# SCH_Atmega_board.net
KiCad netlist of a schematic drawn in Altium Designer
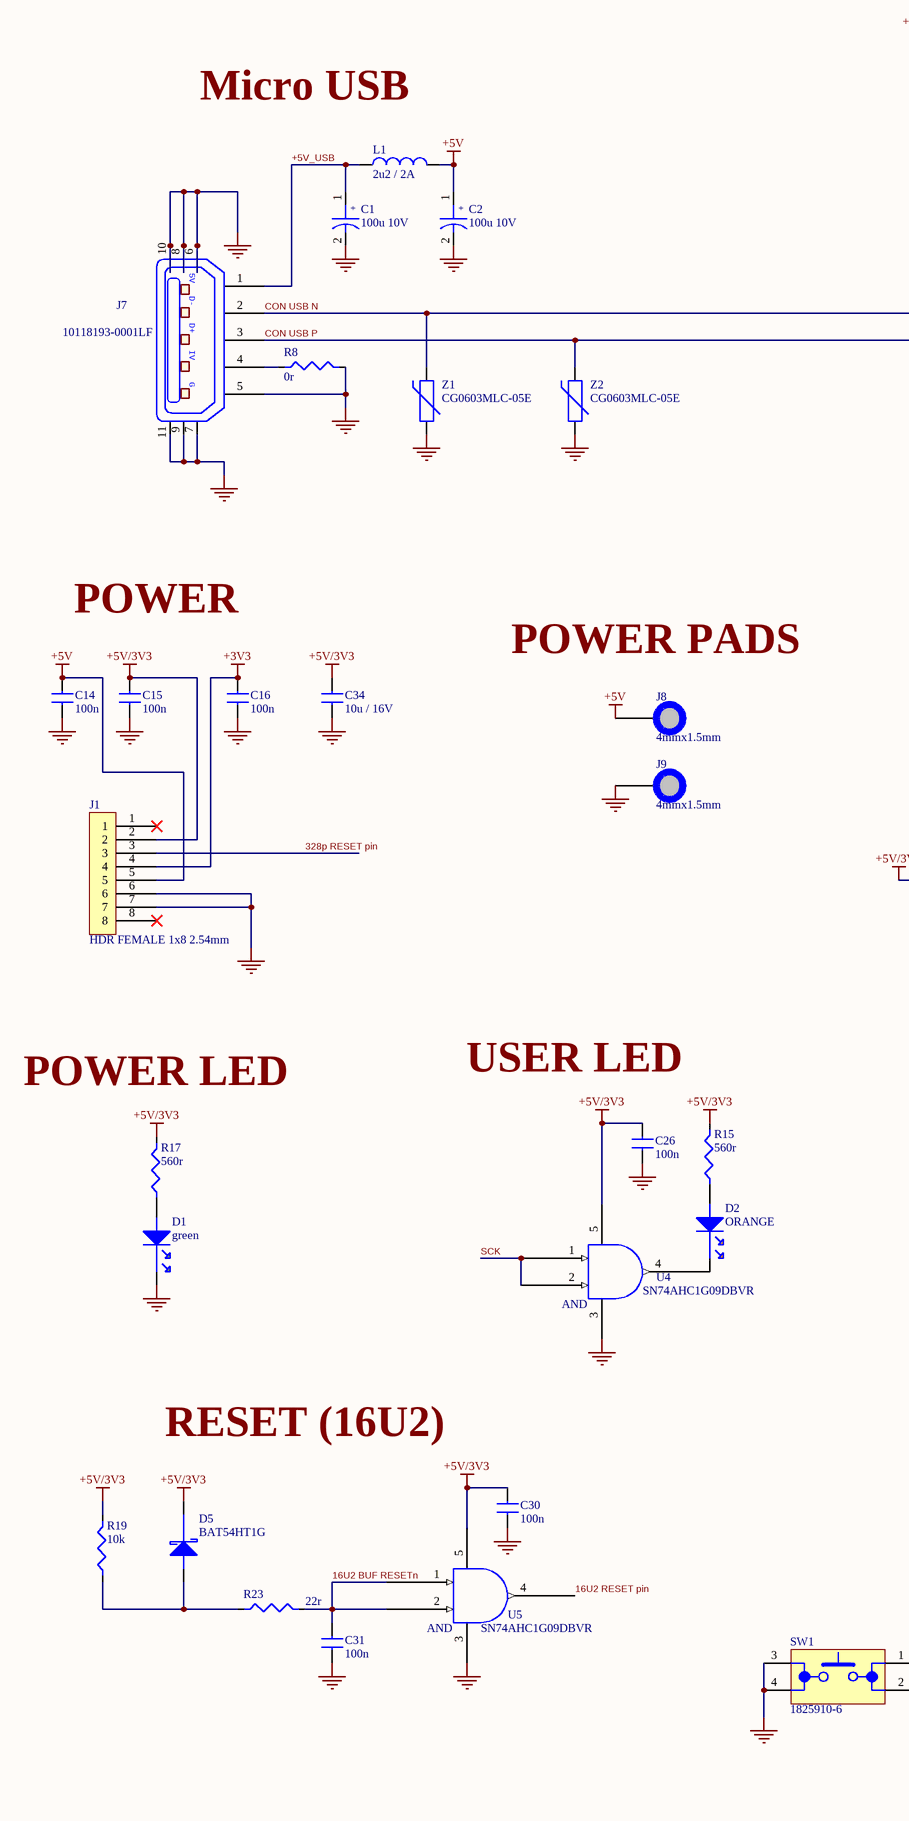
[diagram p0: SCH_Atmega_board.SchDoc, left]
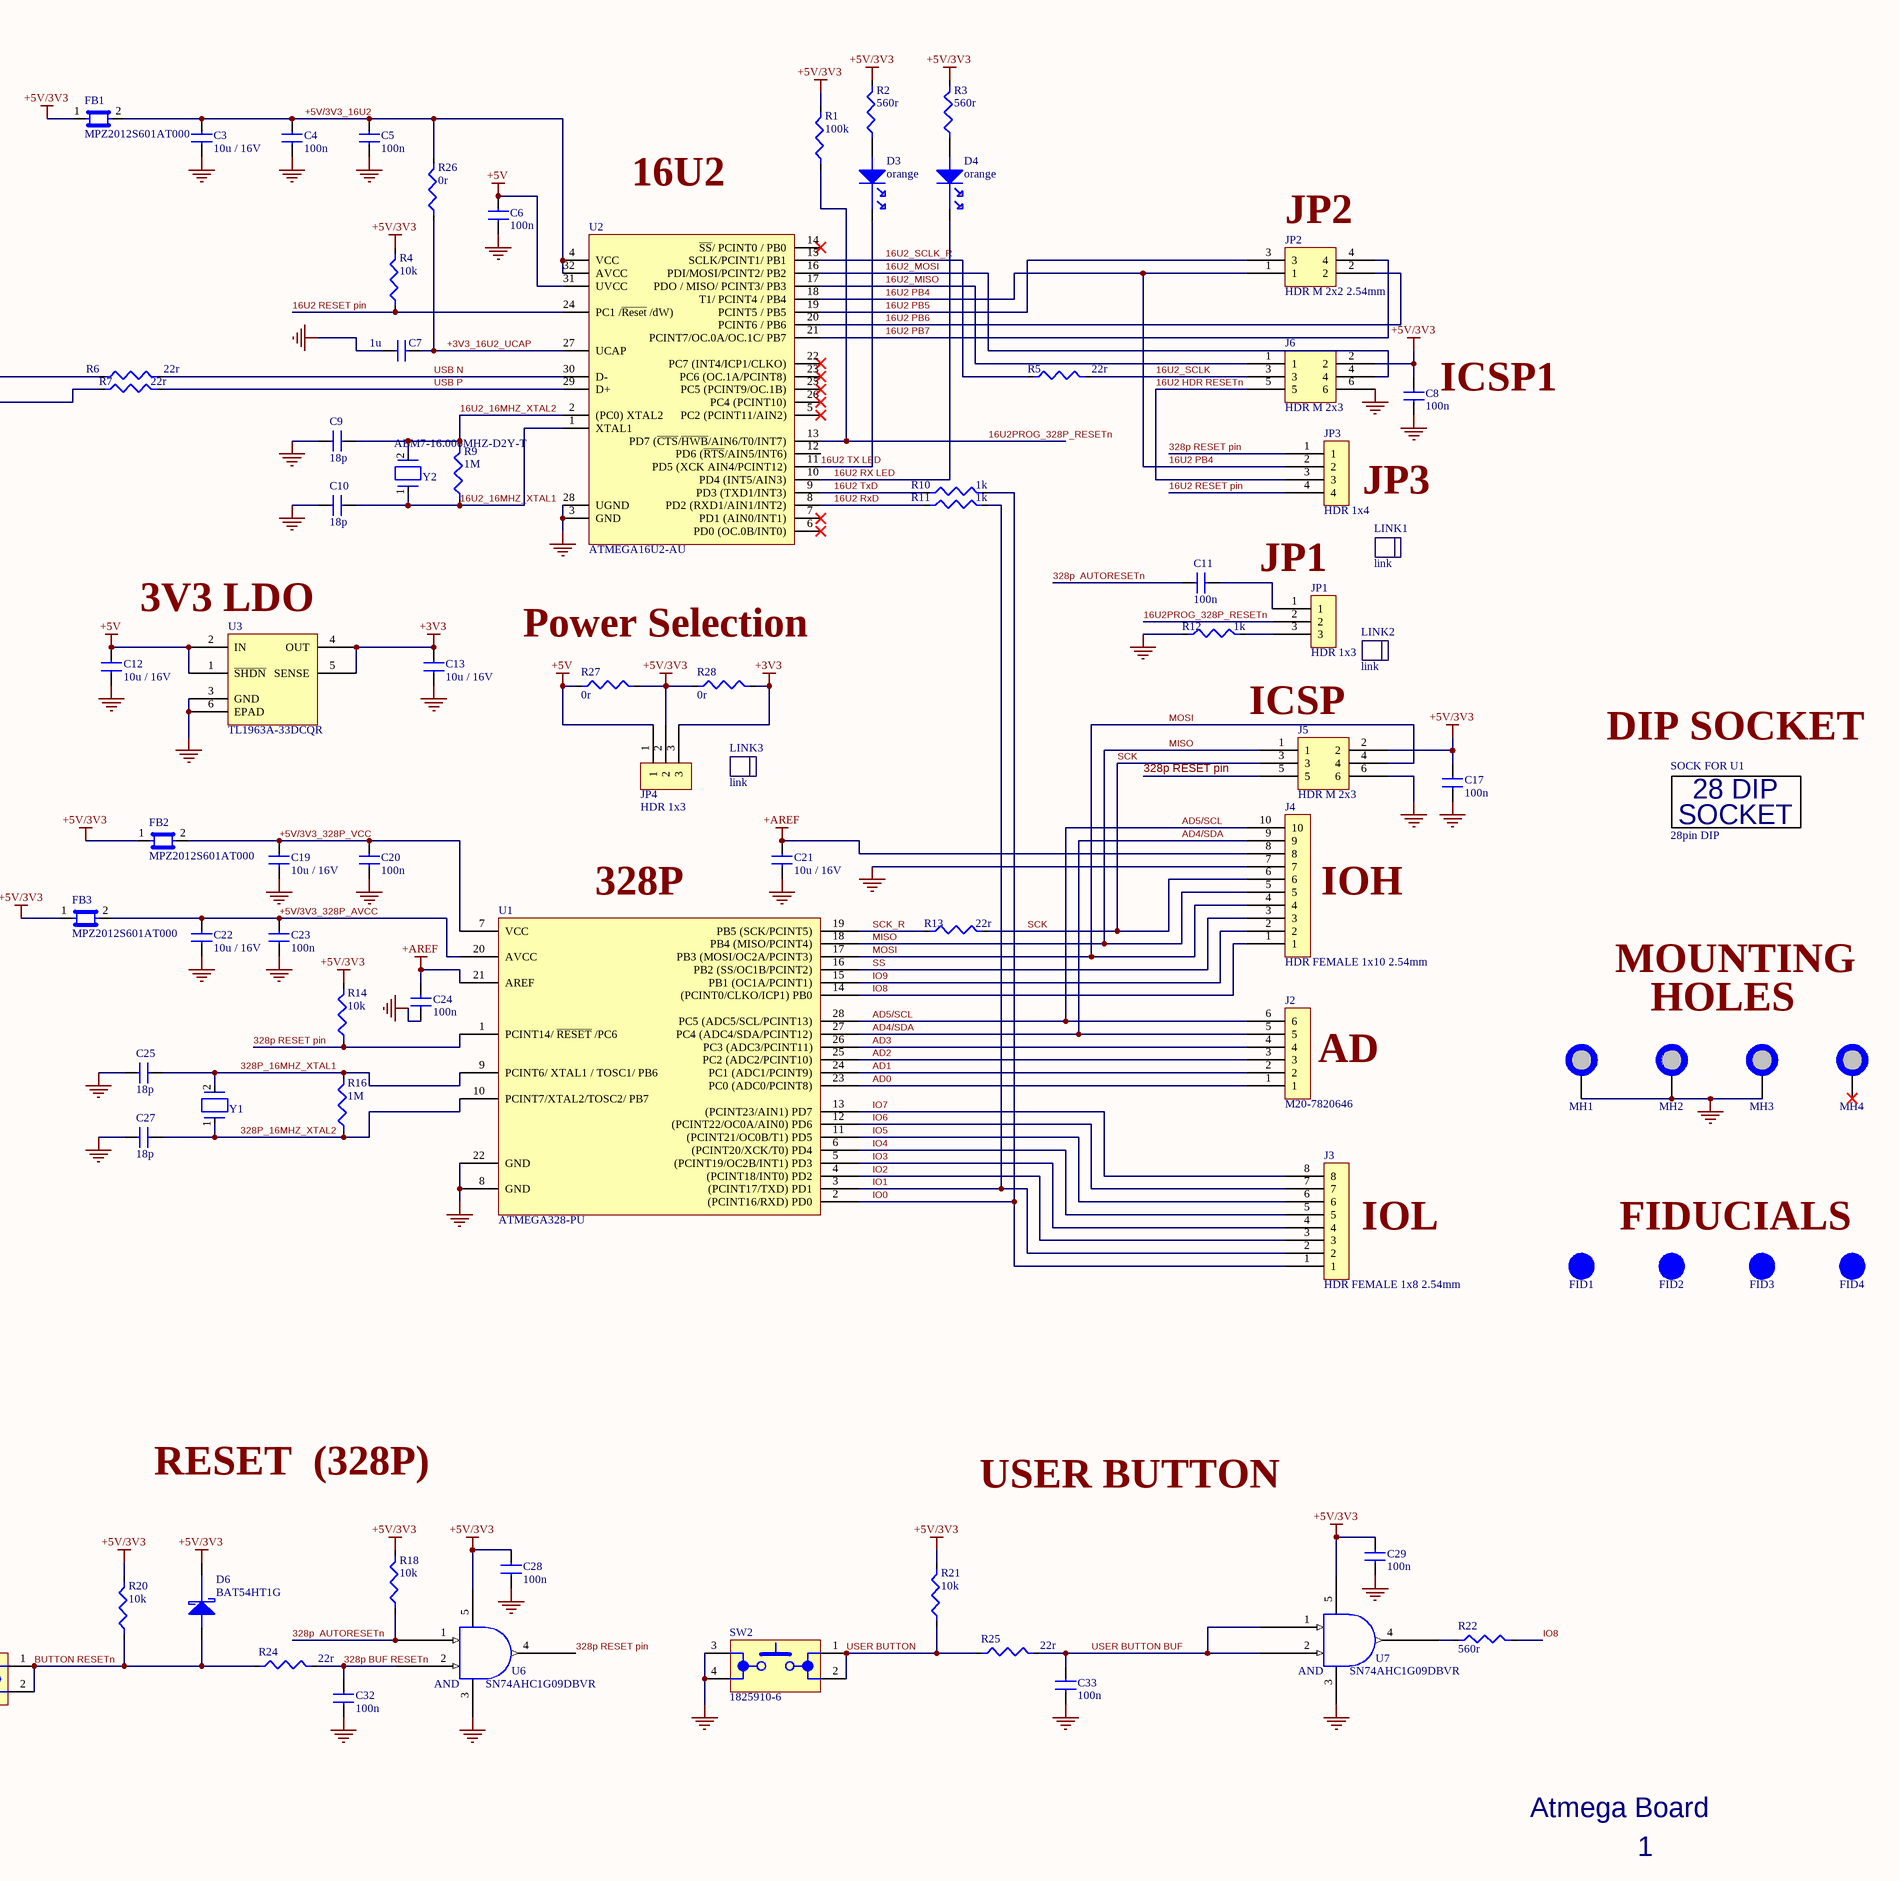
[diagram p1: SCH_Atmega_board.SchDoc, right]

(export (version "E")
  (design (tool "Eeschema 10.0.6"))
  (components
    (comp (ref "C1")
      (value "100u 10V")
      (footprint "C_ALU_C_size")
      (description "Cap Aluminum 100uF 10V 20% (5 X 5.4mm) SMD 50mA 1000 hr 85°C T/R")
      (fields
        (field (name "MANUFACTURER") "Panasonic")
        (field (name "MANUFACTURER PART NUMBER") "EEE-1AA101WR")
      )
      (libsource (lib "SCH_lib_atmega_board") (part "EEE-1AA101WR"))
    )
    (comp (ref "C2")
      (value "100u 10V")
      (footprint "C_ALU_C_size")
      (description "Cap Aluminum 100uF 10V 20% (5 X 5.4mm) SMD 50mA 1000 hr 85°C T/R")
      (fields
        (field (name "MANUFACTURER") "Panasonic")
        (field (name "MANUFACTURER PART NUMBER") "EEE-1AA101WR")
      )
      (libsource (lib "SCH_lib_atmega_board") (part "EEE-1AA101WR"))
    )
    (comp (ref "C3")
      (value "10u / 16V")
      (footprint "C 0805 10u")
      (fields
        (field (name "MANUFACTURER") "TDK")
        (field (name "MANUFACTURER PART NUMBER") "CGA4J1X5R1C106K125AC")
        (field (name "TOLERANCE") "10%")
      )
      (libsource (lib "SCH_lib_atmega_board") (part "CGA4J1X5R1C106K125AC"))
    )
    (comp (ref "C4")
      (value "100n")
      (footprint "C 0805")
      (fields
        (field (name "MANUFACTURER") "TDK")
        (field (name "MANUFACTURER PART NUMBER") "C2012X7R1H104K085AA")
        (field (name "TOLERANCE") "10%")
      )
      (libsource (lib "SCH_lib_atmega_board") (part "C2012X7R1H104K085AA"))
    )
    (comp (ref "C5")
      (value "100n")
      (footprint "C 0805")
      (fields
        (field (name "MANUFACTURER") "TDK")
        (field (name "MANUFACTURER PART NUMBER") "C2012X7R1H104K085AA")
        (field (name "TOLERANCE") "10%")
      )
      (libsource (lib "SCH_lib_atmega_board") (part "C2012X7R1H104K085AA"))
    )
    (comp (ref "C6")
      (value "100n")
      (footprint "C 0805")
      (fields
        (field (name "MANUFACTURER") "TDK")
        (field (name "MANUFACTURER PART NUMBER") "C2012X7R1H104K085AA")
        (field (name "TOLERANCE") "10%")
      )
      (libsource (lib "SCH_lib_atmega_board") (part "C2012X7R1H104K085AA"))
    )
    (comp (ref "C7")
      (value "1u")
      (footprint "C 0805")
      (fields
        (field (name "MANUFACTURER") "TDK")
        (field (name "MANUFACTURER PART NUMBER") "C2012X5R1E105K125AA")
        (field (name "TOLERANCE") "10%")
      )
      (libsource (lib "SCH_lib_atmega_board") (part "C2012X5R1E105K125AA"))
    )
    (comp (ref "C8")
      (value "100n")
      (footprint "C 0805")
      (fields
        (field (name "MANUFACTURER") "TDK")
        (field (name "MANUFACTURER PART NUMBER") "C2012X7R1H104K085AA")
        (field (name "TOLERANCE") "10%")
      )
      (libsource (lib "SCH_lib_atmega_board") (part "C2012X7R1H104K085AA"))
    )
    (comp (ref "C9")
      (value "18p")
      (footprint "C 0805")
      (description "CAP CER 18PF 50V C0G/NP0 0805")
      (fields
        (field (name "MANUFACTURER") "KEMET")
        (field (name "MANUFACTURER PART NUMBER") "C0805C180J5GACTU")
      )
      (libsource (lib "SCH_lib_atmega_board") (part "C0805C180J5GACTU"))
    )
    (comp (ref "C10")
      (value "18p")
      (footprint "C 0805")
      (description "CAP CER 18PF 50V C0G/NP0 0805")
      (fields
        (field (name "MANUFACTURER") "KEMET")
        (field (name "MANUFACTURER PART NUMBER") "C0805C180J5GACTU")
      )
      (libsource (lib "SCH_lib_atmega_board") (part "C0805C180J5GACTU"))
    )
    (comp (ref "C11")
      (value "100n")
      (footprint "C 0805")
      (fields
        (field (name "MANUFACTURER") "TDK")
        (field (name "MANUFACTURER PART NUMBER") "C2012X7R1H104K085AA")
        (field (name "TOLERANCE") "10%")
      )
      (libsource (lib "SCH_lib_atmega_board") (part "C2012X7R1H104K085AA"))
    )
    (comp (ref "C12")
      (value "10u / 16V")
      (footprint "C 0805 10u")
      (fields
        (field (name "MANUFACTURER") "TDK")
        (field (name "MANUFACTURER PART NUMBER") "CGA4J1X5R1C106K125AC")
        (field (name "TOLERANCE") "10%")
      )
      (libsource (lib "SCH_lib_atmega_board") (part "CGA4J1X5R1C106K125AC"))
    )
    (comp (ref "C13")
      (value "10u / 16V")
      (footprint "C 0805 10u")
      (fields
        (field (name "MANUFACTURER") "TDK")
        (field (name "MANUFACTURER PART NUMBER") "CGA4J1X5R1C106K125AC")
        (field (name "TOLERANCE") "10%")
      )
      (libsource (lib "SCH_lib_atmega_board") (part "CGA4J1X5R1C106K125AC"))
    )
    (comp (ref "C14")
      (value "100n")
      (footprint "C 0805")
      (fields
        (field (name "MANUFACTURER") "TDK")
        (field (name "MANUFACTURER PART NUMBER") "C2012X7R1H104K085AA")
        (field (name "TOLERANCE") "10%")
      )
      (libsource (lib "SCH_lib_atmega_board") (part "C2012X7R1H104K085AA"))
    )
    (comp (ref "C15")
      (value "100n")
      (footprint "C 0805")
      (fields
        (field (name "MANUFACTURER") "TDK")
        (field (name "MANUFACTURER PART NUMBER") "C2012X7R1H104K085AA")
        (field (name "TOLERANCE") "10%")
      )
      (libsource (lib "SCH_lib_atmega_board") (part "C2012X7R1H104K085AA"))
    )
    (comp (ref "C16")
      (value "100n")
      (footprint "C 0805")
      (fields
        (field (name "MANUFACTURER") "TDK")
        (field (name "MANUFACTURER PART NUMBER") "C2012X7R1H104K085AA")
        (field (name "TOLERANCE") "10%")
      )
      (libsource (lib "SCH_lib_atmega_board") (part "C2012X7R1H104K085AA"))
    )
    (comp (ref "C17")
      (value "100n")
      (footprint "C 0805")
      (fields
        (field (name "MANUFACTURER") "TDK")
        (field (name "MANUFACTURER PART NUMBER") "C2012X7R1H104K085AA")
        (field (name "TOLERANCE") "10%")
      )
      (libsource (lib "SCH_lib_atmega_board") (part "C2012X7R1H104K085AA"))
    )
    (comp (ref "C19")
      (value "10u / 16V")
      (footprint "C 0805 10u")
      (fields
        (field (name "MANUFACTURER") "TDK")
        (field (name "MANUFACTURER PART NUMBER") "CGA4J1X5R1C106K125AC")
        (field (name "TOLERANCE") "10%")
      )
      (libsource (lib "SCH_lib_atmega_board") (part "CGA4J1X5R1C106K125AC"))
    )
    (comp (ref "C20")
      (value "100n")
      (footprint "C 0805")
      (fields
        (field (name "MANUFACTURER") "TDK")
        (field (name "MANUFACTURER PART NUMBER") "C2012X7R1H104K085AA")
        (field (name "TOLERANCE") "10%")
      )
      (libsource (lib "SCH_lib_atmega_board") (part "C2012X7R1H104K085AA"))
    )
    (comp (ref "C21")
      (value "10u / 16V")
      (footprint "C 0805 10u")
      (fields
        (field (name "MANUFACTURER") "TDK")
        (field (name "MANUFACTURER PART NUMBER") "CGA4J1X5R1C106K125AC")
        (field (name "TOLERANCE") "10%")
      )
      (libsource (lib "SCH_lib_atmega_board") (part "CGA4J1X5R1C106K125AC"))
    )
    (comp (ref "C22")
      (value "10u / 16V")
      (footprint "C 0805 10u")
      (fields
        (field (name "MANUFACTURER") "TDK")
        (field (name "MANUFACTURER PART NUMBER") "CGA4J1X5R1C106K125AC")
        (field (name "TOLERANCE") "10%")
      )
      (libsource (lib "SCH_lib_atmega_board") (part "CGA4J1X5R1C106K125AC"))
    )
    (comp (ref "C23")
      (value "100n")
      (footprint "C 0805")
      (fields
        (field (name "MANUFACTURER") "TDK")
        (field (name "MANUFACTURER PART NUMBER") "C2012X7R1H104K085AA")
        (field (name "TOLERANCE") "10%")
      )
      (libsource (lib "SCH_lib_atmega_board") (part "C2012X7R1H104K085AA"))
    )
    (comp (ref "C24")
      (value "100n")
      (footprint "C 0805")
      (fields
        (field (name "MANUFACTURER") "TDK")
        (field (name "MANUFACTURER PART NUMBER") "C2012X7R1H104K085AA")
        (field (name "TOLERANCE") "10%")
      )
      (libsource (lib "SCH_lib_atmega_board") (part "C2012X7R1H104K085AA"))
    )
    (comp (ref "C25")
      (value "18p")
      (footprint "C 0805")
      (description "CAP CER 18PF 50V C0G/NP0 0805")
      (fields
        (field (name "MANUFACTURER") "KEMET")
        (field (name "MANUFACTURER PART NUMBER") "C0805C180J5GACTU")
      )
      (libsource (lib "SCH_lib_atmega_board") (part "C0805C180J5GACTU"))
    )
    (comp (ref "C26")
      (value "100n")
      (footprint "C 0805")
      (fields
        (field (name "MANUFACTURER") "TDK")
        (field (name "MANUFACTURER PART NUMBER") "C2012X7R1H104K085AA")
        (field (name "TOLERANCE") "10%")
      )
      (libsource (lib "SCH_lib_atmega_board") (part "C2012X7R1H104K085AA"))
    )
    (comp (ref "C27")
      (value "18p")
      (footprint "C 0805")
      (description "CAP CER 18PF 50V C0G/NP0 0805")
      (fields
        (field (name "MANUFACTURER") "KEMET")
        (field (name "MANUFACTURER PART NUMBER") "C0805C180J5GACTU")
      )
      (libsource (lib "SCH_lib_atmega_board") (part "C0805C180J5GACTU"))
    )
    (comp (ref "C28")
      (value "100n")
      (footprint "C 0805")
      (fields
        (field (name "MANUFACTURER") "TDK")
        (field (name "MANUFACTURER PART NUMBER") "C2012X7R1H104K085AA")
        (field (name "TOLERANCE") "10%")
      )
      (libsource (lib "SCH_lib_atmega_board") (part "C2012X7R1H104K085AA"))
    )
    (comp (ref "C29")
      (value "100n")
      (footprint "C 0805")
      (fields
        (field (name "MANUFACTURER") "TDK")
        (field (name "MANUFACTURER PART NUMBER") "C2012X7R1H104K085AA")
        (field (name "TOLERANCE") "10%")
      )
      (libsource (lib "SCH_lib_atmega_board") (part "C2012X7R1H104K085AA"))
    )
    (comp (ref "C30")
      (value "100n")
      (footprint "C 0805")
      (fields
        (field (name "MANUFACTURER") "TDK")
        (field (name "MANUFACTURER PART NUMBER") "C2012X7R1H104K085AA")
        (field (name "TOLERANCE") "10%")
      )
      (libsource (lib "SCH_lib_atmega_board") (part "C2012X7R1H104K085AA"))
    )
    (comp (ref "C31")
      (value "100n")
      (footprint "C 0805")
      (fields
        (field (name "MANUFACTURER") "TDK")
        (field (name "MANUFACTURER PART NUMBER") "C2012X7R1H104K085AA")
        (field (name "TOLERANCE") "10%")
      )
      (libsource (lib "SCH_lib_atmega_board") (part "C2012X7R1H104K085AA"))
    )
    (comp (ref "C32")
      (value "100n")
      (footprint "C 0805")
      (fields
        (field (name "MANUFACTURER") "TDK")
        (field (name "MANUFACTURER PART NUMBER") "C2012X7R1H104K085AA")
        (field (name "TOLERANCE") "10%")
      )
      (libsource (lib "SCH_lib_atmega_board") (part "C2012X7R1H104K085AA"))
    )
    (comp (ref "C33")
      (value "100n")
      (footprint "C 0805")
      (fields
        (field (name "MANUFACTURER") "TDK")
        (field (name "MANUFACTURER PART NUMBER") "C2012X7R1H104K085AA")
        (field (name "TOLERANCE") "10%")
      )
      (libsource (lib "SCH_lib_atmega_board") (part "C2012X7R1H104K085AA"))
    )
    (comp (ref "C34")
      (value "10u / 16V")
      (footprint "C 0805 10u")
      (fields
        (field (name "MANUFACTURER") "TDK")
        (field (name "MANUFACTURER PART NUMBER") "CGA4J1X5R1C106K125AC")
        (field (name "TOLERANCE") "10%")
      )
      (libsource (lib "SCH_lib_atmega_board") (part "CGA4J1X5R1C106K125AC"))
    )
    (comp (ref "D1")
      (value "green")
      (footprint "LED 0803")
      (description "LED Uni-Color Green 572nm 2-Pin Chip 0603(1608Metric) T/R")
      (fields
        (field (name "MANUFACTURER") "Osram Opto")
        (field (name "MANUFACTURER PART NUMBER") "LGL29K-G2J1-24-Z")
      )
      (libsource (lib "SCH_lib_atmega_board") (part "LGL29K-G2J1-24-Z"))
    )
    (comp (ref "D2")
      (value "ORANGE")
      (footprint "LED 0803")
      (description "LED Orange CLEAR SMD")
      (fields
        (field (name "MANUFACTURER") "Vishay Lite-On")
        (field (name "MANUFACTURER PART NUMBER") "LTST-C191KSKT")
      )
      (libsource (lib "SCH_lib_atmega_board") (part "LTST-C191KSKT"))
    )
    (comp (ref "D3")
      (value "orange")
      (footprint "LED 0803")
      (description "LED Orange CLEAR SMD")
      (fields
        (field (name "MANUFACTURER") "Vishay Lite-On")
        (field (name "MANUFACTURER PART NUMBER") "LTST-C191KSKT")
      )
      (libsource (lib "SCH_lib_atmega_board") (part "LTST-C191KSKT"))
    )
    (comp (ref "D4")
      (value "orange")
      (footprint "LED 0803")
      (description "LED Orange CLEAR SMD")
      (fields
        (field (name "MANUFACTURER") "Vishay Lite-On")
        (field (name "MANUFACTURER PART NUMBER") "LTST-C191KSKT")
      )
      (libsource (lib "SCH_lib_atmega_board") (part "LTST-C191KSKT"))
    )
    (comp (ref "D5")
      (value "BAT54HT1G")
      (footprint "SOD323_diode")
      (description "Small Signal Schottky Diode, Single, 30 V, 200 mA, 800 mV, 600 mA, 150 C ;RoHS Compliant: Yes")
      (fields (field (name "MANUFACTURER") "ON Semiconductor / Fairchild"))
      (libsource (lib "SCH_lib_atmega_board") (part "BAT54HT1G"))
    )
    (comp (ref "D6")
      (value "BAT54HT1G")
      (footprint "SOD323_diode")
      (description "Small Signal Schottky Diode, Single, 30 V, 200 mA, 800 mV, 600 mA, 150 C ;RoHS Compliant: Yes")
      (fields (field (name "MANUFACTURER") "ON Semiconductor / Fairchild"))
      (libsource (lib "SCH_lib_atmega_board") (part "BAT54HT1G"))
    )
    (comp (ref "FB1")
      (value "MPZ2012S601AT000")
      (footprint "EPCOS_MPZ2012_IPC_A")
      (description "FERRITE BEAD 600 OHM 0805 1LN")
      (fields (field (name "MANUFACTURER") "TDK"))
      (libsource (lib "SCH_lib_atmega_board") (part "MPZ2012S601AT000"))
    )
    (comp (ref "FB2")
      (value "MPZ2012S601AT000")
      (footprint "EPCOS_MPZ2012_IPC_A")
      (description "FERRITE BEAD 600 OHM 0805 1LN")
      (fields (field (name "MANUFACTURER") "TDK"))
      (libsource (lib "SCH_lib_atmega_board") (part "MPZ2012S601AT000"))
    )
    (comp (ref "FB3")
      (value "MPZ2012S601AT000")
      (footprint "EPCOS_MPZ2012_IPC_A")
      (description "FERRITE BEAD 600 OHM 0805 1LN")
      (fields (field (name "MANUFACTURER") "TDK"))
      (libsource (lib "SCH_lib_atmega_board") (part "MPZ2012S601AT000"))
    )
    (comp (ref "FID1")
      (value "FID_1mm")
      (footprint "FID_40x120")
      (description "Fiducial 40mil Diameter 120mm mask")
      (libsource (lib "SCH_lib_atmega_board") (part "FID_1mm"))
    )
    (comp (ref "FID2")
      (value "FID_1mm")
      (footprint "FID_40x120")
      (description "Fiducial 40mil Diameter 120mm mask")
      (libsource (lib "SCH_lib_atmega_board") (part "FID_1mm"))
    )
    (comp (ref "FID3")
      (value "FID_1mm")
      (footprint "FID_40x120")
      (description "Fiducial 40mil Diameter 120mm mask")
      (libsource (lib "SCH_lib_atmega_board") (part "FID_1mm"))
    )
    (comp (ref "FID4")
      (value "FID_1mm")
      (footprint "FID_40x120")
      (description "Fiducial 40mil Diameter 120mm mask")
      (libsource (lib "SCH_lib_atmega_board") (part "FID_1mm"))
    )
    (comp (ref "J1")
      (value "HDR FEMALE 1x8 2.54mm")
      (footprint "HDR_F_1x8_2.54mm - duplicate")
      (description "2.54mm (0.1\") Pitch SIL Vertical PC Tail Socket Assembly, selective gold + tin, 8 contacts")
      (fields (field (name "MANUFACTURER") "Harwin") (field (name "MANUFACTURER PART NUMBER") "M20-7820842"))
      (libsource (lib "") (part "M20-7820842_1"))
    )
    (comp (ref "J2")
      (value "M20-7820646")
      (footprint "HDR_F_1x6_2.54mm")
      (description "06-WAY SIL VERT SOCKET L/FREE")
      (fields (field (name "MANUFACTURER") "Harwin"))
      (libsource (lib "SCH_lib_atmega_board") (part "M20-7820646"))
    )
    (comp (ref "J3")
      (value "HDR FEMALE 1x8 2.54mm")
      (footprint "HDR_F_1x8_2.54mm - duplicate")
      (description "2.54mm (0.1\") Pitch SIL Vertical PC Tail Socket Assembly, selective gold + tin, 8 contacts")
      (fields (field (name "MANUFACTURER") "Harwin") (field (name "MANUFACTURER PART NUMBER") "M20-7820842"))
      (libsource (lib "SCH_lib_atmega_board") (part "M20-7820842"))
    )
    (comp (ref "J4")
      (value "HDR FEMALE 1x10 2.54mm")
      (footprint "HDR_F_1x10_2.54mm - duplicate")
      (fields (field (name "MANUFACTURER") "Harwin") (field (name "MANUFACTURER PART NUMBER") "M20-7821046"))
      (libsource (lib "SCH_lib_atmega_board") (part "M20-7821046"))
    )
    (comp (ref "J5")
      (value "HDR M 2x3")
      (footprint "HDR 2x3 M 2.54mm")
      (description "Board-board Connector Header, 6 Position, 2ROW")
      (fields
        (field (name "MANUFACTURER") "Amphenol ICC")
        (field (name "MANUFACTURER PART NUMBER") "67997-106HLF")
      )
      (libsource (lib "SCH_lib_atmega_board") (part "67997-106HLF"))
    )
    (comp (ref "J6")
      (value "HDR M 2x3")
      (footprint "HDR 2x3 M 2.54mm")
      (description "Board-board Connector Header, 6 Position, 2ROW")
      (fields
        (field (name "MANUFACTURER") "Amphenol ICC")
        (field (name "MANUFACTURER PART NUMBER") "67997-106HLF")
      )
      (libsource (lib "SCH_lib_atmega_board") (part "67997-106HLF"))
    )
    (comp (ref "J7")
      (value "10118193-0001LF")
      (footprint "10118193")
      (description "CONN USB MICRO B RECPT SMT R/A")
      (fields (field (name "MANUFACTURER") "Amphenol ICC / FCI"))
      (libsource (lib "SCH_lib_atmega_board") (part "10118193-0001LF"))
    )
    (comp (ref "J8")
      (value "4mmx1.5mm")
      (footprint "PAD_WITH_HOLE_4mm_1.5mm")
      (description "pad with a hole")
      (libsource (lib "SCH_lib_atmega_board") (part "PAD_WITH HOLE_4mm_1.5mm"))
    )
    (comp (ref "J9")
      (value "4mmx1.5mm")
      (footprint "PAD_WITH_HOLE_4mm_1.5mm")
      (description "pad with a hole")
      (libsource (lib "SCH_lib_atmega_board") (part "PAD_WITH HOLE_4mm_1.5mm"))
    )
    (comp (ref "JP1")
      (value "HDR 1x3")
      (footprint "HDR_F_1x3_2.54mm")
      (fields
        (field (name "MANUFACTURER") "Amphenol ICC")
        (field (name "MANUFACTURER PART NUMBER") "68000-103HLF")
      )
      (libsource (lib "SCH_lib_atmega_board") (part "68000-103HLF"))
    )
    (comp (ref "JP2")
      (value "HDR M 2x2 2.54mm")
      (footprint "HDR 2x2 M 2.54mm")
      (description "Conn Unshrouded Header HDR 4 POS 2.54mm Solder ST Thru-Hole Poly Bag")
      (fields
        (field (name "MANUFACTURER") "Amphenol ICC / FCI")
        (field (name "MANUFACTURER PART NUMBER") "68602-204HLF")
      )
      (libsource (lib "SCH_lib_atmega_board") (part "68602-204HLF"))
    )
    (comp (ref "JP3")
      (value "HDR 1x4")
      (footprint "HDR_F_1x4_2.54mm")
      (fields
        (field (name "MANUFACTURER") "Amphenol ICC / FCI")
        (field (name "MANUFACTURER PART NUMBER") "68001-204HLF")
      )
      (libsource (lib "SCH_lib_atmega_board") (part "68001-204HLF"))
    )
    (comp (ref "JP4")
      (value "HDR 1x3")
      (footprint "HDR_F_1x3_2.54mm")
      (fields
        (field (name "MANUFACTURER") "Amphenol ICC")
        (field (name "MANUFACTURER PART NUMBER") "68000-103HLF")
      )
      (libsource (lib "") (part "68000-103HLF_1"))
    )
    (comp (ref "L1")
      (value "2u2 / 2A")
      (footprint "C1210_IND")
      (description "FIXED IND 2.2UH 2A 80 MOHM SMD")
      (fields
        (field (name "MANUFACTURER") "KEMET")
        (field (name "MANUFACTURER PART NUMBER") "L1210R2R2MDWIT")
      )
      (libsource (lib "SCH_lib_atmega_board") (part "L1210R2R2MDWIT"))
    )
    (comp (ref "LINK1")
      (value "link")
      (description "CONN JUMPER SHORTING .100\" GOLD")
      (fields
        (field (name "MANUFACTURER") "Sullins")
        (field (name "MANUFACTURER PART NUMBER") "QPC02SXGN-RC")
      )
      (libsource (lib "SCH_lib_atmega_board") (part "QPC02SXGN-RC"))
    )
    (comp (ref "LINK2")
      (value "link")
      (description "CONN JUMPER SHORTING .100\" GOLD")
      (fields
        (field (name "MANUFACTURER") "Sullins")
        (field (name "MANUFACTURER PART NUMBER") "QPC02SXGN-RC")
      )
      (libsource (lib "SCH_lib_atmega_board") (part "QPC02SXGN-RC"))
    )
    (comp (ref "LINK3")
      (value "link")
      (description "CONN JUMPER SHORTING .100\" GOLD")
      (fields
        (field (name "MANUFACTURER") "Sullins")
        (field (name "MANUFACTURER PART NUMBER") "QPC02SXGN-RC")
      )
      (libsource (lib "SCH_lib_atmega_board") (part "QPC02SXGN-RC"))
    )
    (comp (ref "MH1")
      (value "MH_7.4MMC_3.2MMD")
      (footprint "MH7_7.4mmD_3.2mmD")
      (description "mounting hole 7.4mm dia 3.2mm drill")
      (libsource (lib "SCH_lib_atmega_board") (part "MOUNTING_HOLE_7.4_3.2"))
    )
    (comp (ref "MH2")
      (value "MH_7.4MMC_3.2MMD")
      (footprint "MH7_7.4mmD_3.2mmD")
      (description "mounting hole 7.4mm dia 3.2mm drill")
      (libsource (lib "SCH_lib_atmega_board") (part "MOUNTING_HOLE_7.4_3.2"))
    )
    (comp (ref "MH3")
      (value "MH_7.4MMC_3.2MMD")
      (footprint "MH7_7.4mmD_3.2mmD")
      (description "mounting hole 7.4mm dia 3.2mm drill")
      (libsource (lib "SCH_lib_atmega_board") (part "MOUNTING_HOLE_7.4_3.2"))
    )
    (comp (ref "MH4")
      (value "MH 7.4 NON Plated")
      (footprint "MH_7.4 3.2_non copper no plated")
      (description "hole 7.4 mm diameter. Non copper 3.2mm non plated")
      (libsource (lib "SCH_lib_atmega_board") (part "MH_7.4 _non plated"))
    )
    (comp (ref "R1")
      (value "100k")
      (footprint "R0805")
      (description "Res Thick Film 0805 100K Ohm 1% 1/8W ±100ppm/°C Molded SMD Paper T/R")
      (fields
        (field (name "MANUFACTURER") "Yageo")
        (field (name "MANUFACTURER PART NUMBER") "RC0805FR-07100KL")
      )
      (libsource (lib "SCH_lib_atmega_board") (part "RC0805FR-07100KL"))
    )
    (comp (ref "R2")
      (value "560r")
      (footprint "R0805")
      (description "Surface Mount Thick Film Resistor, RC Series, 560 ohm, 125 mW, - 1%, 150 V, 0805 [2012 Metric]")
      (fields
        (field (name "MANUFACTURER") "Yageo")
        (field (name "MANUFACTURER PART NUMBER") "RC0805FR-07560RL")
      )
      (libsource (lib "SCH_lib_atmega_board") (part "RC0805FR-07560RL"))
    )
    (comp (ref "R3")
      (value "560r")
      (footprint "R0805")
      (description "Surface Mount Thick Film Resistor, RC Series, 560 ohm, 125 mW, - 1%, 150 V, 0805 [2012 Metric]")
      (fields
        (field (name "MANUFACTURER") "Yageo")
        (field (name "MANUFACTURER PART NUMBER") "RC0805FR-07560RL")
      )
      (libsource (lib "SCH_lib_atmega_board") (part "RC0805FR-07560RL"))
    )
    (comp (ref "R4")
      (value "10k")
      (footprint "R0805")
      (description "RES SMD 10K OHM 1% 1/8W 0805")
      (fields
        (field (name "MANUFACTURER") "Yageo")
        (field (name "MANUFACTURER PART NUMBER") "RC0805FR-0710KL")
      )
      (libsource (lib "SCH_lib_atmega_board") (part "RC0805FR-0710KL"))
    )
    (comp (ref "R5")
      (value "22r")
      (footprint "R0805")
      (description "RES SMD 22 OHM 1% 1/8W 0805")
      (fields
        (field (name "MANUFACTURER") "Yageo")
        (field (name "MANUFACTURER PART NUMBER") "RT0805FRE0722RL")
      )
      (libsource (lib "SCH_lib_atmega_board") (part "RT0805FRE0722RL"))
    )
    (comp (ref "R6")
      (value "22r")
      (footprint "R0805")
      (description "RES SMD 22 OHM 1% 1/8W 0805")
      (fields
        (field (name "MANUFACTURER") "Yageo")
        (field (name "MANUFACTURER PART NUMBER") "RT0805FRE0722RL")
      )
      (libsource (lib "SCH_lib_atmega_board") (part "RT0805FRE0722RL"))
    )
    (comp (ref "R7")
      (value "22r")
      (footprint "R0805")
      (description "RES SMD 22 OHM 1% 1/8W 0805")
      (fields
        (field (name "MANUFACTURER") "Yageo")
        (field (name "MANUFACTURER PART NUMBER") "RT0805FRE0722RL")
      )
      (libsource (lib "SCH_lib_atmega_board") (part "RT0805FRE0722RL"))
    )
    (comp (ref "R8")
      (value "0r")
      (footprint "R0805")
      (description "Surface Mount Thick Film Resistor, RC Series, 125 mW, - 5%, 150 V, 0805 [2012 Metric]")
      (fields
        (field (name "MANUFACTURER") "Yageo")
        (field (name "MANUFACTURER PART NUMBER") "RC0805JR-070RL")
      )
      (libsource (lib "SCH_lib_atmega_board") (part "RC0805JR-070RL"))
    )
    (comp (ref "R9")
      (value "1M")
      (footprint "R0805")
      (description "Res Thick Film 0805 1M Ohm 1% 0.125W(1/8W) ±100ppm/C Epoxy SMD T/R")
      (fields
        (field (name "MANUFACTURER") "Yageo Phycomp")
        (field (name "MANUFACTURER PART NUMBER") "RC0805FR-071ML")
      )
      (libsource (lib "SCH_lib_atmega_board") (part "RC0805FR-071ML"))
    )
    (comp (ref "R10")
      (value "1k")
      (footprint "R0805")
      (fields
        (field (name "MANUFACTURER") "Yageo")
        (field (name "MANUFACTURER PART NUMBER") "RC0805FR-071KL")
        (field (name "TOLERANCE") "1%")
      )
      (libsource (lib "SCH_lib_atmega_board") (part "RC0805FR-071KL"))
    )
    (comp (ref "R11")
      (value "1k")
      (footprint "R0805")
      (fields
        (field (name "MANUFACTURER") "Yageo")
        (field (name "MANUFACTURER PART NUMBER") "RC0805FR-071KL")
        (field (name "TOLERANCE") "1%")
      )
      (libsource (lib "SCH_lib_atmega_board") (part "RC0805FR-071KL"))
    )
    (comp (ref "R12")
      (value "1k")
      (footprint "R0805")
      (fields
        (field (name "MANUFACTURER") "Yageo")
        (field (name "MANUFACTURER PART NUMBER") "RC0805FR-071KL")
        (field (name "TOLERANCE") "1%")
      )
      (libsource (lib "SCH_lib_atmega_board") (part "RC0805FR-071KL"))
    )
    (comp (ref "R13")
      (value "22r")
      (footprint "R0805")
      (description "RES SMD 22 OHM 1% 1/8W 0805")
      (fields
        (field (name "MANUFACTURER") "Yageo")
        (field (name "MANUFACTURER PART NUMBER") "RT0805FRE0722RL")
      )
      (libsource (lib "SCH_lib_atmega_board") (part "RT0805FRE0722RL"))
    )
    (comp (ref "R14")
      (value "10k")
      (footprint "R0805")
      (description "RES SMD 10K OHM 1% 1/8W 0805")
      (fields
        (field (name "MANUFACTURER") "Yageo")
        (field (name "MANUFACTURER PART NUMBER") "RC0805FR-0710KL")
      )
      (libsource (lib "SCH_lib_atmega_board") (part "RC0805FR-0710KL"))
    )
    (comp (ref "R15")
      (value "560r")
      (footprint "R0805")
      (description "Surface Mount Thick Film Resistor, RC Series, 560 ohm, 125 mW, - 1%, 150 V, 0805 [2012 Metric]")
      (fields
        (field (name "MANUFACTURER") "Yageo")
        (field (name "MANUFACTURER PART NUMBER") "RC0805FR-07560RL")
      )
      (libsource (lib "SCH_lib_atmega_board") (part "RC0805FR-07560RL"))
    )
    (comp (ref "R16")
      (value "1M")
      (footprint "R0805")
      (description "Res Thick Film 0805 1M Ohm 1% 0.125W(1/8W) ±100ppm/C Epoxy SMD T/R")
      (fields
        (field (name "MANUFACTURER") "Yageo Phycomp")
        (field (name "MANUFACTURER PART NUMBER") "RC0805FR-071ML")
      )
      (libsource (lib "SCH_lib_atmega_board") (part "RC0805FR-071ML"))
    )
    (comp (ref "R17")
      (value "560r")
      (footprint "R0805")
      (description "Surface Mount Thick Film Resistor, RC Series, 560 ohm, 125 mW, - 1%, 150 V, 0805 [2012 Metric]")
      (fields
        (field (name "MANUFACTURER") "Yageo")
        (field (name "MANUFACTURER PART NUMBER") "RC0805FR-07560RL")
      )
      (libsource (lib "SCH_lib_atmega_board") (part "RC0805FR-07560RL"))
    )
    (comp (ref "R18")
      (value "10k")
      (footprint "R0805")
      (description "RES SMD 10K OHM 1% 1/8W 0805")
      (fields
        (field (name "MANUFACTURER") "Yageo")
        (field (name "MANUFACTURER PART NUMBER") "RC0805FR-0710KL")
      )
      (libsource (lib "SCH_lib_atmega_board") (part "RC0805FR-0710KL"))
    )
    (comp (ref "R19")
      (value "10k")
      (footprint "R0805")
      (description "RES SMD 10K OHM 1% 1/8W 0805")
      (fields
        (field (name "MANUFACTURER") "Yageo")
        (field (name "MANUFACTURER PART NUMBER") "RC0805FR-0710KL")
      )
      (libsource (lib "SCH_lib_atmega_board") (part "RC0805FR-0710KL"))
    )
    (comp (ref "R20")
      (value "10k")
      (footprint "R0805")
      (description "RES SMD 10K OHM 1% 1/8W 0805")
      (fields
        (field (name "MANUFACTURER") "Yageo")
        (field (name "MANUFACTURER PART NUMBER") "RC0805FR-0710KL")
      )
      (libsource (lib "SCH_lib_atmega_board") (part "RC0805FR-0710KL"))
    )
    (comp (ref "R21")
      (value "10k")
      (footprint "R0805")
      (description "RES SMD 10K OHM 1% 1/8W 0805")
      (fields
        (field (name "MANUFACTURER") "Yageo")
        (field (name "MANUFACTURER PART NUMBER") "RC0805FR-0710KL")
      )
      (libsource (lib "SCH_lib_atmega_board") (part "RC0805FR-0710KL"))
    )
    (comp (ref "R22")
      (value "560r")
      (footprint "R0805")
      (description "Surface Mount Thick Film Resistor, RC Series, 560 ohm, 125 mW, - 1%, 150 V, 0805 [2012 Metric]")
      (fields
        (field (name "MANUFACTURER") "Yageo")
        (field (name "MANUFACTURER PART NUMBER") "RC0805FR-07560RL")
      )
      (libsource (lib "SCH_lib_atmega_board") (part "RC0805FR-07560RL"))
    )
    (comp (ref "R23")
      (value "22r")
      (footprint "R0805")
      (description "RES SMD 22 OHM 1% 1/8W 0805")
      (fields
        (field (name "MANUFACTURER") "Yageo")
        (field (name "MANUFACTURER PART NUMBER") "RT0805FRE0722RL")
      )
      (libsource (lib "SCH_lib_atmega_board") (part "RT0805FRE0722RL"))
    )
    (comp (ref "R24")
      (value "22r")
      (footprint "R0805")
      (description "RES SMD 22 OHM 1% 1/8W 0805")
      (fields
        (field (name "MANUFACTURER") "Yageo")
        (field (name "MANUFACTURER PART NUMBER") "RT0805FRE0722RL")
      )
      (libsource (lib "SCH_lib_atmega_board") (part "RT0805FRE0722RL"))
    )
    (comp (ref "R25")
      (value "22r")
      (footprint "R0805")
      (description "RES SMD 22 OHM 1% 1/8W 0805")
      (fields
        (field (name "MANUFACTURER") "Yageo")
        (field (name "MANUFACTURER PART NUMBER") "RT0805FRE0722RL")
      )
      (libsource (lib "SCH_lib_atmega_board") (part "RT0805FRE0722RL"))
    )
    (comp (ref "R26")
      (value "0r")
      (footprint "R0805")
      (description "Surface Mount Thick Film Resistor, RC Series, 125 mW, - 5%, 150 V, 0805 [2012 Metric]")
      (fields
        (field (name "MANUFACTURER") "Yageo")
        (field (name "MANUFACTURER PART NUMBER") "RC0805JR-070RL")
      )
      (libsource (lib "SCH_lib_atmega_board") (part "RC0805JR-070RL"))
    )
    (comp (ref "R27")
      (value "0r")
      (footprint "R0805")
      (description "Surface Mount Thick Film Resistor, RC Series, 125 mW, - 5%, 150 V, 0805 [2012 Metric]")
      (fields
        (field (name "MANUFACTURER") "Yageo")
        (field (name "MANUFACTURER PART NUMBER") "RC0805JR-070RL")
      )
      (libsource (lib "SCH_lib_atmega_board") (part "RC0805JR-070RL"))
    )
    (comp (ref "R28")
      (value "0r")
      (footprint "R0805")
      (description "Surface Mount Thick Film Resistor, RC Series, 125 mW, - 5%, 150 V, 0805 [2012 Metric]")
      (fields
        (field (name "MANUFACTURER") "Yageo")
        (field (name "MANUFACTURER PART NUMBER") "RC0805JR-070RL")
      )
      (libsource (lib "SCH_lib_atmega_board") (part "RC0805JR-070RL"))
    )
    (comp (ref "SOCK FOR U1")
      (value "28pin DIP")
      (footprint "28 dip 7.62 mm socket")
      (description "CONN IC DIP SOCKET 28POS TIN")
      (fields (field (name "MANUFACTURER") "3M") (field (name "MANUFACTURER PART NUMBER") "4828-3004-CP"))
      (libsource (lib "SCH_lib_atmega_board") (part "4828-3004-CP"))
    )
    (comp (ref "SW1")
      (value "1825910-6")
      (footprint "DIP4")
      (description "6X6, H5,  160G TAC.SWITCH")
      (fields (field (name "MANUFACTURER") "TE Connectivity Alcoswitch"))
      (libsource (lib "SCH_lib_atmega_board") (part "1825910-6"))
    )
    (comp (ref "SW2")
      (value "1825910-6")
      (footprint "DIP4")
      (description "6X6, H5,  160G TAC.SWITCH")
      (fields (field (name "MANUFACTURER") "TE Connectivity Alcoswitch"))
      (libsource (lib "SCH_lib_atmega_board") (part "1825910-6"))
    )
    (comp (ref "U1")
      (value "ATMEGA328-PU")
      (footprint "ATMEGA328P_DIP")
      (description "MCU 8-bit ATmega AVR RISC 32KB Flash 2.5V/3.3V/5V 28-Pin PDIP")
      (fields (field (name "MANUFACTURER") "Microchip / Atmel"))
      (libsource (lib "SCH_lib_atmega_board") (part "ATMEGA328-PU"))
    )
    (comp (ref "U2")
      (value "ATMEGA16U2-AU")
      (footprint "TQFP32")
      (description "MICROCHIP - ATMEGA16U2-AU - MCU, 8BIT, MEGAAVR, 16MHZ, TQFP-32")
      (fields (field (name "MANUFACTURER") "Microchip / Atmel"))
      (libsource (lib "SCH_lib_atmega_board") (part "ATMEGA16U2-AU"))
    )
    (comp (ref "U3")
      (value "TL1963A-33DCQR")
      (footprint "DCQ (R-PDSO-G6)")
      (description "IC REG LINEAR 3.3V 1.5A SOT223-6")
      (fields (field (name "MANUFACTURER") "Texas Instruments"))
      (libsource (lib "SCH_lib_atmega_board") (part "TL1963A-33DCQR"))
    )
    (comp (ref "U4")
      (value "SN74AHC1G09DBVR")
      (footprint "DBV_SOT_235")
      (description "TEXAS INSTRUMENTS - SN74AHC1G09DBVR - AND Gate, 74AHC1G09, 2 Input, 2 V to 5.5 V, SOT-23-5")
      (fields (field (name "MANUFACTURER") "Texas Instruments"))
      (libsource (lib "SCH_lib_atmega_board") (part "SN74AHC1G09DBVR"))
    )
    (comp (ref "U5")
      (value "SN74AHC1G09DBVR")
      (footprint "DBV_SOT_235")
      (description "TEXAS INSTRUMENTS - SN74AHC1G09DBVR - AND Gate, 74AHC1G09, 2 Input, 2 V to 5.5 V, SOT-23-5")
      (fields (field (name "MANUFACTURER") "Texas Instruments"))
      (libsource (lib "SCH_lib_atmega_board") (part "SN74AHC1G09DBVR"))
    )
    (comp (ref "U6")
      (value "SN74AHC1G09DBVR")
      (footprint "DBV_SOT_235")
      (description "TEXAS INSTRUMENTS - SN74AHC1G09DBVR - AND Gate, 74AHC1G09, 2 Input, 2 V to 5.5 V, SOT-23-5")
      (fields (field (name "MANUFACTURER") "Texas Instruments"))
      (libsource (lib "SCH_lib_atmega_board") (part "SN74AHC1G09DBVR"))
    )
    (comp (ref "U7")
      (value "SN74AHC1G09DBVR")
      (footprint "DBV_SOT_235")
      (description "TEXAS INSTRUMENTS - SN74AHC1G09DBVR - AND Gate, 74AHC1G09, 2 Input, 2 V to 5.5 V, SOT-23-5")
      (fields (field (name "MANUFACTURER") "Texas Instruments"))
      (libsource (lib "SCH_lib_atmega_board") (part "SN74AHC1G09DBVR"))
    )
    (comp (ref "Y1")
      (value "ABM7-16.000MHZ-D2Y-T")
      (footprint "ABM7_v1_1_BIG")
      (description "CRYSTAL 16.0000MHZ 18PF SMD")
      (fields (field (name "MANUFACTURER") "Abracon") (field (name "TOLERANCE") "20ppm"))
      (libsource (lib "SCH_lib_atmega_board") (part "ABM7-16.000MHZ-D2Y-T"))
    )
    (comp (ref "Y2")
      (value "ABM7-16.000MHZ-D2Y-T")
      (footprint "ABM7_v1_1_BIG")
      (description "CRYSTAL 16.0000MHZ 18PF SMD")
      (fields (field (name "MANUFACTURER") "Abracon") (field (name "TOLERANCE") "20ppm"))
      (libsource (lib "SCH_lib_atmega_board") (part "ABM7-16.000MHZ-D2Y-T"))
    )
    (comp (ref "Z1")
      (value "CG0603MLC-05E")
      (footprint "R0603")
      (description "VARISTOR 0603")
      (fields (field (name "MANUFACTURER") "Bourns") (field (name "VOLTAGE") "5V"))
      (libsource (lib "SCH_lib_atmega_board") (part "CG0603MLC-05E"))
    )
    (comp (ref "Z2")
      (value "CG0603MLC-05E")
      (footprint "R0603")
      (description "VARISTOR 0603")
      (fields (field (name "MANUFACTURER") "Bourns") (field (name "VOLTAGE") "5V"))
      (libsource (lib "SCH_lib_atmega_board") (part "CG0603MLC-05E"))
    )
  )
  (nets
    (net (code "1") (name "+3V3") (class "Default")
      (node (ref "C13") (pin "2") (pinfunction "2_2") (pintype "passive"))
      (node (ref "C16") (pin "2") (pinfunction "2_2") (pintype "passive"))
      (node (ref "J1") (pin "4") (pinfunction "4_4") (pintype "passive"))
      (node (ref "JP4") (pin "3") (pinfunction "3_3") (pintype "passive"))
      (node (ref "R28") (pin "2") (pinfunction "2_2") (pintype "passive"))
      (node (ref "U3") (pin "4") (pinfunction "OUT_4") (pintype "passive"))
      (node (ref "U3") (pin "5") (pinfunction "SENSE_5") (pintype "passive"))
    )
    (net (code "2") (name "+5V") (class "Default")
      (node (ref "C12") (pin "2") (pinfunction "2_2") (pintype "passive"))
      (node (ref "C14") (pin "2") (pinfunction "2_2") (pintype "passive"))
      (node (ref "C2") (pin "1") (pinfunction "1_1") (pintype "passive"))
      (node (ref "C6") (pin "2") (pinfunction "2_2") (pintype "passive"))
      (node (ref "J1") (pin "5") (pinfunction "5_5") (pintype "passive"))
      (node (ref "J8") (pin "1") (pinfunction "1_1") (pintype "passive"))
      (node (ref "JP4") (pin "1") (pinfunction "1_1") (pintype "passive"))
      (node (ref "L1") (pin "2") (pinfunction "2_2") (pintype "passive"))
      (node (ref "R27") (pin "1") (pinfunction "1_1") (pintype "passive"))
      (node (ref "U2") (pin "31") (pinfunction "UVCC_31") (pintype "power_in"))
      (node (ref "U3") (pin "1") (pinfunction "~{SHDN}_1") (pintype "passive"))
      (node (ref "U3") (pin "2") (pinfunction "IN_2") (pintype "passive"))
    )
    (net (code "3") (name "+5V{slash}3V3") (class "Default")
      (node (ref "C15") (pin "2") (pinfunction "2_2") (pintype "passive"))
      (node (ref "C17") (pin "2") (pinfunction "2_2") (pintype "passive"))
      (node (ref "C26") (pin "2") (pinfunction "2_2") (pintype "passive"))
      (node (ref "C28") (pin "2") (pinfunction "2_2") (pintype "passive"))
      (node (ref "C29") (pin "2") (pinfunction "2_2") (pintype "passive"))
      (node (ref "C30") (pin "2") (pinfunction "2_2") (pintype "passive"))
      (node (ref "C34") (pin "2") (pinfunction "2_2") (pintype "passive"))
      (node (ref "C8") (pin "2") (pinfunction "2_2") (pintype "passive"))
      (node (ref "D5") (pin "2") (pinfunction "Cathode_2") (pintype "passive"))
      (node (ref "D6") (pin "2") (pinfunction "Cathode_2") (pintype "passive"))
      (node (ref "FB1") (pin "1") (pinfunction "1_1") (pintype "passive"))
      (node (ref "FB2") (pin "1") (pinfunction "1_1") (pintype "passive"))
      (node (ref "FB3") (pin "1") (pinfunction "1_1") (pintype "passive"))
      (node (ref "J1") (pin "2") (pinfunction "2_2") (pintype "passive"))
      (node (ref "J5") (pin "2") (pinfunction "2_2") (pintype "passive"))
      (node (ref "J6") (pin "2") (pinfunction "2_2") (pintype "passive"))
      (node (ref "JP4") (pin "2") (pinfunction "2_2") (pintype "passive"))
      (node (ref "R1") (pin "2") (pinfunction "2_2") (pintype "passive"))
      (node (ref "R14") (pin "2") (pinfunction "2_2") (pintype "passive"))
      (node (ref "R15") (pin "2") (pinfunction "2_2") (pintype "passive"))
      (node (ref "R17") (pin "2") (pinfunction "2_2") (pintype "passive"))
      (node (ref "R18") (pin "2") (pinfunction "2_2") (pintype "passive"))
      (node (ref "R19") (pin "2") (pinfunction "2_2") (pintype "passive"))
      (node (ref "R2") (pin "2") (pinfunction "2_2") (pintype "passive"))
      (node (ref "R20") (pin "2") (pinfunction "2_2") (pintype "passive"))
      (node (ref "R21") (pin "2") (pinfunction "2_2") (pintype "passive"))
      (node (ref "R27") (pin "2") (pinfunction "2_2") (pintype "passive"))
      (node (ref "R28") (pin "1") (pinfunction "1_1") (pintype "passive"))
      (node (ref "R3") (pin "2") (pinfunction "2_2") (pintype "passive"))
      (node (ref "R4") (pin "2") (pinfunction "2_2") (pintype "passive"))
      (node (ref "U4") (pin "5") (pinfunction "5_5") (pintype "passive"))
      (node (ref "U5") (pin "5") (pinfunction "5_5") (pintype "passive"))
      (node (ref "U6") (pin "5") (pinfunction "5_5") (pintype "passive"))
      (node (ref "U7") (pin "5") (pinfunction "5_5") (pintype "passive"))
    )
    (net (code "4") (name "+AREF") (class "Default")
      (node (ref "C21") (pin "2") (pinfunction "2_2") (pintype "passive"))
      (node (ref "C24") (pin "2") (pinfunction "2_2") (pintype "passive"))
      (node (ref "J4") (pin "8") (pinfunction "8_8") (pintype "passive"))
      (node (ref "U1") (pin "21") (pinfunction "AREF_21") (pintype "passive"))
    )
    (net (code "5") (name "/+3V3_16U2_UCAP") (class "Default")
      (node (ref "C7") (pin "2") (pinfunction "2_2") (pintype "passive"))
      (node (ref "R26") (pin "1") (pinfunction "1_1") (pintype "passive"))
      (node (ref "U2") (pin "27") (pinfunction "UCAP_27") (pintype "power_in"))
    )
    (net (code "6") (name "/+5V_USB") (class "Default")
      (node (ref "C1") (pin "1") (pinfunction "1_1") (pintype "passive"))
      (node (ref "J7") (pin "1") (pinfunction "1_1") (pintype "passive"))
      (node (ref "L1") (pin "1") (pinfunction "1_1") (pintype "passive"))
    )
    (net (code "7") (name "/+5V{slash}3V3_16U2") (class "Default")
      (node (ref "C3") (pin "2") (pinfunction "2_2") (pintype "passive"))
      (node (ref "C4") (pin "2") (pinfunction "2_2") (pintype "passive"))
      (node (ref "C5") (pin "2") (pinfunction "2_2") (pintype "passive"))
      (node (ref "FB1") (pin "2") (pinfunction "2_2") (pintype "passive"))
      (node (ref "R26") (pin "2") (pinfunction "2_2") (pintype "passive"))
      (node (ref "U2") (pin "32") (pinfunction "AVCC_32") (pintype "power_in"))
      (node (ref "U2") (pin "4") (pinfunction "VCC_4") (pintype "power_in"))
    )
    (net (code "8") (name "/+5V{slash}3V3_328P_AVCC") (class "Default")
      (node (ref "C22") (pin "2") (pinfunction "2_2") (pintype "passive"))
      (node (ref "C23") (pin "2") (pinfunction "2_2") (pintype "passive"))
      (node (ref "FB3") (pin "2") (pinfunction "2_2") (pintype "passive"))
      (node (ref "U1") (pin "20") (pinfunction "AVCC_20") (pintype "passive"))
    )
    (net (code "9") (name "/+5V{slash}3V3_328P_VCC") (class "Default")
      (node (ref "C19") (pin "2") (pinfunction "2_2") (pintype "passive"))
      (node (ref "C20") (pin "2") (pinfunction "2_2") (pintype "passive"))
      (node (ref "FB2") (pin "2") (pinfunction "2_2") (pintype "passive"))
      (node (ref "U1") (pin "7") (pinfunction "VCC_7") (pintype "passive"))
    )
    (net (code "10") (name "/16U2 BUF RESETn") (class "Default")
      (node (ref "C31") (pin "2") (pinfunction "2_2") (pintype "passive"))
      (node (ref "R23") (pin "2") (pinfunction "2_2") (pintype "passive"))
      (node (ref "U5") (pin "1") (pinfunction "1_1") (pintype "input"))
      (node (ref "U5") (pin "2") (pinfunction "2_2") (pintype "input"))
    )
    (net (code "11") (name "/16U2 HDR RESETn") (class "Default")
      (node (ref "J6") (pin "5") (pinfunction "5_5") (pintype "passive"))
      (node (ref "JP3") (pin "3") (pinfunction "3_3") (pintype "passive"))
    )
    (net (code "12") (name "/16U2 PB4") (class "Default")
      (node (ref "JP2") (pin "1") (pinfunction "1_1") (pintype "passive"))
      (node (ref "JP3") (pin "2") (pinfunction "2_2") (pintype "passive"))
      (node (ref "U2") (pin "18") (pinfunction "T1/_PCINT4_/_PB4_18") (pintype "passive"))
    )
    (net (code "13") (name "/16U2 PB5") (class "Default")
      (node (ref "JP2") (pin "3") (pinfunction "3_3") (pintype "passive"))
      (node (ref "U2") (pin "19") (pinfunction "PCINT5_/_PB5_19") (pintype "passive"))
    )
    (net (code "14") (name "/16U2 PB6") (class "Default")
      (node (ref "JP2") (pin "2") (pinfunction "2_2") (pintype "passive"))
      (node (ref "U2") (pin "20") (pinfunction "PCINT6_/_PB6_20") (pintype "passive"))
    )
    (net (code "15") (name "/16U2 PB7") (class "Default")
      (node (ref "JP2") (pin "4") (pinfunction "4_4") (pintype "passive"))
      (node (ref "U2") (pin "21") (pinfunction "PCINT7/OC.0A/OC.1C/_PB7_21") (pintype "passive"))
    )
    (net (code "16") (name "/16U2 RESET pin") (class "Default")
      (node (ref "JP3") (pin "4") (pinfunction "4_4") (pintype "passive"))
      (node (ref "R4") (pin "1") (pinfunction "1_1") (pintype "passive"))
      (node (ref "U2") (pin "24") (pinfunction "PC1_/~{Reset}_/dW)_24") (pintype "passive"))
      (node (ref "U5") (pin "4") (pinfunction "4_4") (pintype "output"))
    )
    (net (code "17") (name "/16U2 RX LED") (class "Default")
      (node (ref "D4") (pin "2") (pinfunction "Cathode_2") (pintype "passive"))
      (node (ref "U2") (pin "10") (pinfunction "PD4_(INT5/AIN3)_10") (pintype "passive"))
    )
    (net (code "18") (name "/16U2 RxD") (class "Default")
      (node (ref "R11") (pin "1") (pinfunction "1_1") (pintype "passive"))
      (node (ref "U2") (pin "8") (pinfunction "PD2_(RXD1/AIN1/INT2)_8") (pintype "passive"))
    )
    (net (code "19") (name "/16U2 TX LED") (class "Default")
      (node (ref "D3") (pin "2") (pinfunction "Cathode_2") (pintype "passive"))
      (node (ref "U2") (pin "11") (pinfunction "PD5_(XCK_AIN4/PCINT12)_11") (pintype "passive"))
    )
    (net (code "20") (name "/16U2 TxD") (class "Default")
      (node (ref "R10") (pin "1") (pinfunction "1_1") (pintype "passive"))
      (node (ref "U2") (pin "9") (pinfunction "PD3_(TXD1/INT3)_9") (pintype "passive"))
    )
    (net (code "21") (name "/16U2PROG_328P_RESETn") (class "Default")
      (node (ref "JP1") (pin "2") (pinfunction "2_2") (pintype "passive"))
      (node (ref "R1") (pin "1") (pinfunction "1_1") (pintype "passive"))
      (node (ref "U2") (pin "13") (pinfunction "PD7_(~{CTS}/~{HWB}/AIN6/T0/INT7)_13") (pintype "passive"))
    )
    (net (code "22") (name "/16U2_16MHZ_XTAL1") (class "Default")
      (node (ref "C10") (pin "2") (pinfunction "2_2") (pintype "passive"))
      (node (ref "R9") (pin "1") (pinfunction "1_1") (pintype "passive"))
      (node (ref "U2") (pin "1") (pinfunction "XTAL1_1") (pintype "passive"))
      (node (ref "Y2") (pin "1") (pinfunction "1_1") (pintype "passive"))
    )
    (net (code "23") (name "/16U2_16MHZ_XTAL2") (class "Default")
      (node (ref "C9") (pin "2") (pinfunction "2_2") (pintype "passive"))
      (node (ref "R9") (pin "2") (pinfunction "2_2") (pintype "passive"))
      (node (ref "U2") (pin "2") (pinfunction "(PC0)_XTAL2_2") (pintype "passive"))
      (node (ref "Y2") (pin "2") (pinfunction "2_2") (pintype "passive"))
    )
    (net (code "24") (name "/16U2_MISO") (class "Default")
      (node (ref "J6") (pin "1") (pinfunction "1_1") (pintype "passive"))
      (node (ref "U2") (pin "17") (pinfunction "PDO_/_MISO/_PCINT3/_PB3_17") (pintype "passive"))
    )
    (net (code "25") (name "/16U2_MOSI") (class "Default")
      (node (ref "J6") (pin "4") (pinfunction "4_4") (pintype "passive"))
      (node (ref "U2") (pin "16") (pinfunction "PDI/MOSI/PCINT2/_PB2_16") (pintype "passive"))
    )
    (net (code "26") (name "/16U2_SCLK") (class "Default")
      (node (ref "J6") (pin "3") (pinfunction "3_3") (pintype "passive"))
      (node (ref "R5") (pin "2") (pinfunction "2_2") (pintype "passive"))
    )
    (net (code "27") (name "/16U2_SCLK_R") (class "Default")
      (node (ref "R5") (pin "1") (pinfunction "1_1") (pintype "passive"))
      (node (ref "U2") (pin "15") (pinfunction "SCLK/PCINT1/_PB1_15") (pintype "passive"))
    )
    (net (code "28") (name "/328P_16MHZ_XTAL1") (class "Default")
      (node (ref "C25") (pin "2") (pinfunction "2_2") (pintype "passive"))
      (node (ref "R16") (pin "2") (pinfunction "2_2") (pintype "passive"))
      (node (ref "U1") (pin "9") (pinfunction "PCINT6/_XTAL1_/_TOSC1/_PB6_9") (pintype "passive"))
      (node (ref "Y1") (pin "2") (pinfunction "2_2") (pintype "passive"))
    )
    (net (code "29") (name "/328P_16MHZ_XTAL2") (class "Default")
      (node (ref "C27") (pin "2") (pinfunction "2_2") (pintype "passive"))
      (node (ref "R16") (pin "1") (pinfunction "1_1") (pintype "passive"))
      (node (ref "U1") (pin "10") (pinfunction "PCINT7/XTAL2/TOSC2/_PB7_10") (pintype "passive"))
      (node (ref "Y1") (pin "1") (pinfunction "1_1") (pintype "passive"))
    )
    (net (code "30") (name "/328p  AUTORESETn") (class "Default")
      (node (ref "C11") (pin "1") (pinfunction "1_1") (pintype "passive"))
      (node (ref "R18") (pin "1") (pinfunction "1_1") (pintype "passive"))
      (node (ref "U6") (pin "1") (pinfunction "1_1") (pintype "input"))
    )
    (net (code "31") (name "/328p BUF RESETn") (class "Default")
      (node (ref "C32") (pin "2") (pinfunction "2_2") (pintype "passive"))
      (node (ref "R24") (pin "2") (pinfunction "2_2") (pintype "passive"))
      (node (ref "U6") (pin "2") (pinfunction "2_2") (pintype "input"))
    )
    (net (code "32") (name "/328p RESET pin") (class "Default")
      (node (ref "J1") (pin "3") (pinfunction "3_3") (pintype "passive"))
      (node (ref "J5") (pin "5") (pinfunction "5_5") (pintype "passive"))
      (node (ref "JP3") (pin "1") (pinfunction "1_1") (pintype "passive"))
      (node (ref "R14") (pin "1") (pinfunction "1_1") (pintype "passive"))
      (node (ref "U1") (pin "1") (pinfunction "PCINT14/_~{RESET}_/PC6_1") (pintype "passive"))
      (node (ref "U6") (pin "4") (pinfunction "4_4") (pintype "output"))
    )
    (net (code "33") (name "/AD0") (class "Default")
      (node (ref "J2") (pin "1") (pinfunction "1_1") (pintype "passive"))
      (node (ref "U1") (pin "23") (pinfunction "PC0_(ADC0/PCINT8)_23") (pintype "passive"))
    )
    (net (code "34") (name "/AD1") (class "Default")
      (node (ref "J2") (pin "2") (pinfunction "2_2") (pintype "passive"))
      (node (ref "U1") (pin "24") (pinfunction "PC1_(ADC1/PCINT9)_24") (pintype "passive"))
    )
    (net (code "35") (name "/AD2") (class "Default")
      (node (ref "J2") (pin "3") (pinfunction "3_3") (pintype "passive"))
      (node (ref "U1") (pin "25") (pinfunction "PC2_(ADC2/PCINT10)_25") (pintype "passive"))
    )
    (net (code "36") (name "/AD3") (class "Default")
      (node (ref "J2") (pin "4") (pinfunction "4_4") (pintype "passive"))
      (node (ref "U1") (pin "26") (pinfunction "PC3_(ADC3/PCINT11)_26") (pintype "passive"))
    )
    (net (code "37") (name "/AD4{slash}SDA") (class "Default")
      (node (ref "J2") (pin "5") (pinfunction "5_5") (pintype "passive"))
      (node (ref "J4") (pin "9") (pinfunction "9_9") (pintype "passive"))
      (node (ref "U1") (pin "27") (pinfunction "PC4_(ADC4/SDA/PCINT12)_27") (pintype "passive"))
    )
    (net (code "38") (name "/AD5{slash}SCL") (class "Default")
      (node (ref "J2") (pin "6") (pinfunction "6_6") (pintype "passive"))
      (node (ref "J4") (pin "10") (pinfunction "10_10") (pintype "passive"))
      (node (ref "U1") (pin "28") (pinfunction "PC5_(ADC5/SCL/PCINT13)_28") (pintype "passive"))
    )
    (net (code "39") (name "/BUTTON RESETn") (class "Default")
      (node (ref "D6") (pin "1") (pinfunction "Anode_1") (pintype "passive"))
      (node (ref "R20") (pin "1") (pinfunction "1_1") (pintype "passive"))
      (node (ref "R24") (pin "1") (pinfunction "1_1") (pintype "passive"))
      (node (ref "SW1") (pin "1") (pinfunction "1_1") (pintype "passive"))
      (node (ref "SW1") (pin "2") (pinfunction "2_2") (pintype "passive"))
    )
    (net (code "40") (name "/CON USB N") (class "Default")
      (node (ref "J7") (pin "2") (pinfunction "2_2") (pintype "passive"))
      (node (ref "R6") (pin "1") (pinfunction "1_1") (pintype "passive"))
      (node (ref "Z1") (pin "2") (pinfunction "2_2") (pintype "passive"))
    )
    (net (code "41") (name "/CON USB P") (class "Default")
      (node (ref "J7") (pin "3") (pinfunction "3_3") (pintype "passive"))
      (node (ref "R7") (pin "1") (pinfunction "1_1") (pintype "passive"))
      (node (ref "Z2") (pin "2") (pinfunction "2_2") (pintype "passive"))
    )
    (net (code "42") (name "/IO0") (class "Default")
      (node (ref "J3") (pin "1") (pinfunction "1_1") (pintype "passive"))
      (node (ref "R10") (pin "2") (pinfunction "2_2") (pintype "passive"))
      (node (ref "U1") (pin "2") (pinfunction "(PCINT16/RXD)_PD0_2") (pintype "passive"))
    )
    (net (code "43") (name "/IO1") (class "Default")
      (node (ref "J3") (pin "2") (pinfunction "2_2") (pintype "passive"))
      (node (ref "R11") (pin "2") (pinfunction "2_2") (pintype "passive"))
      (node (ref "U1") (pin "3") (pinfunction "(PCINT17/TXD)_PD1_3") (pintype "passive"))
    )
    (net (code "44") (name "/IO2") (class "Default")
      (node (ref "J3") (pin "3") (pinfunction "3_3") (pintype "passive"))
      (node (ref "U1") (pin "4") (pinfunction "(PCINT18/INT0)_PD2_4") (pintype "passive"))
    )
    (net (code "45") (name "/IO3") (class "Default")
      (node (ref "J3") (pin "4") (pinfunction "4_4") (pintype "passive"))
      (node (ref "U1") (pin "5") (pinfunction "(PCINT19/OC2B/INT1)_PD3_5") (pintype "passive"))
    )
    (net (code "46") (name "/IO4") (class "Default")
      (node (ref "J3") (pin "5") (pinfunction "5_5") (pintype "passive"))
      (node (ref "U1") (pin "6") (pinfunction "(PCINT20/XCK/T0)_PD4_6") (pintype "passive"))
    )
    (net (code "47") (name "/IO5") (class "Default")
      (node (ref "J3") (pin "6") (pinfunction "6_6") (pintype "passive"))
      (node (ref "U1") (pin "11") (pinfunction "(PCINT21/OC0B/T1)_PD5_11") (pintype "passive"))
    )
    (net (code "48") (name "/IO6") (class "Default")
      (node (ref "J3") (pin "7") (pinfunction "7_7") (pintype "passive"))
      (node (ref "U1") (pin "12") (pinfunction "(PCINT22/OC0A/AIN0)_PD6_12") (pintype "passive"))
    )
    (net (code "49") (name "/IO7") (class "Default")
      (node (ref "J3") (pin "8") (pinfunction "8_8") (pintype "passive"))
      (node (ref "U1") (pin "13") (pinfunction "(PCINT23/AIN1)_PD7_13") (pintype "passive"))
    )
    (net (code "50") (name "/IO8") (class "Default")
      (node (ref "J4") (pin "1") (pinfunction "1_1") (pintype "passive"))
      (node (ref "R22") (pin "2") (pinfunction "2_2") (pintype "passive"))
      (node (ref "U1") (pin "14") (pinfunction "(PCINT0/CLKO/ICP1)_PB0_14") (pintype "passive"))
    )
    (net (code "51") (name "/IO9") (class "Default")
      (node (ref "J4") (pin "2") (pinfunction "2_2") (pintype "passive"))
      (node (ref "U1") (pin "15") (pinfunction "PB1_(OC1A/PCINT1)_15") (pintype "passive"))
    )
    (net (code "52") (name "/MISO") (class "Default")
      (node (ref "J4") (pin "5") (pinfunction "5_5") (pintype "passive"))
      (node (ref "J5") (pin "1") (pinfunction "1_1") (pintype "passive"))
      (node (ref "U1") (pin "18") (pinfunction "PB4_(MISO/PCINT4)_18") (pintype "passive"))
    )
    (net (code "53") (name "/MOSI") (class "Default")
      (node (ref "J4") (pin "4") (pinfunction "4_4") (pintype "passive"))
      (node (ref "J5") (pin "4") (pinfunction "4_4") (pintype "passive"))
      (node (ref "U1") (pin "17") (pinfunction "PB3_(MOSI/OC2A/PCINT3)_17") (pintype "passive"))
    )
    (net (code "54") (name "/SCK") (class "Default")
      (node (ref "J4") (pin "6") (pinfunction "6_6") (pintype "passive"))
      (node (ref "J5") (pin "3") (pinfunction "3_3") (pintype "passive"))
      (node (ref "R13") (pin "2") (pinfunction "2_2") (pintype "passive"))
      (node (ref "U4") (pin "1") (pinfunction "1_1") (pintype "input"))
      (node (ref "U4") (pin "2") (pinfunction "2_2") (pintype "input"))
    )
    (net (code "55") (name "/SCK_R") (class "Default")
      (node (ref "R13") (pin "1") (pinfunction "1_1") (pintype "passive"))
      (node (ref "U1") (pin "19") (pinfunction "PB5_(SCK/PCINT5)_19") (pintype "passive"))
    )
    (net (code "56") (name "/SS") (class "Default")
      (node (ref "J4") (pin "3") (pinfunction "3_3") (pintype "passive"))
      (node (ref "U1") (pin "16") (pinfunction "PB2_(SS/OC1B/PCINT2)_16") (pintype "passive"))
    )
    (net (code "57") (name "/USB N") (class "Default")
      (node (ref "R6") (pin "2") (pinfunction "2_2") (pintype "passive"))
      (node (ref "U2") (pin "30") (pinfunction "D-_30") (pintype "passive"))
    )
    (net (code "58") (name "/USB P") (class "Default")
      (node (ref "R7") (pin "2") (pinfunction "2_2") (pintype "passive"))
      (node (ref "U2") (pin "29") (pinfunction "D+_29") (pintype "passive"))
    )
    (net (code "59") (name "/USER BUTTON") (class "Default")
      (node (ref "R21") (pin "1") (pinfunction "1_1") (pintype "passive"))
      (node (ref "R25") (pin "1") (pinfunction "1_1") (pintype "passive"))
      (node (ref "SW2") (pin "1") (pinfunction "1_1") (pintype "passive"))
      (node (ref "SW2") (pin "2") (pinfunction "2_2") (pintype "passive"))
    )
    (net (code "60") (name "/USER BUTTON BUF") (class "Default")
      (node (ref "C33") (pin "2") (pinfunction "2_2") (pintype "passive"))
      (node (ref "R25") (pin "2") (pinfunction "2_2") (pintype "passive"))
      (node (ref "U7") (pin "1") (pinfunction "1_1") (pintype "input"))
      (node (ref "U7") (pin "2") (pinfunction "2_2") (pintype "input"))
    )
    (net (code "61") (name "GND") (class "Default")
      (node (ref "C1") (pin "2") (pinfunction "2_2") (pintype "passive"))
      (node (ref "C10") (pin "1") (pinfunction "1_1") (pintype "passive"))
      (node (ref "C12") (pin "1") (pinfunction "1_1") (pintype "passive"))
      (node (ref "C13") (pin "1") (pinfunction "1_1") (pintype "passive"))
      (node (ref "C14") (pin "1") (pinfunction "1_1") (pintype "passive"))
      (node (ref "C15") (pin "1") (pinfunction "1_1") (pintype "passive"))
      (node (ref "C16") (pin "1") (pinfunction "1_1") (pintype "passive"))
      (node (ref "C17") (pin "1") (pinfunction "1_1") (pintype "passive"))
      (node (ref "C19") (pin "1") (pinfunction "1_1") (pintype "passive"))
      (node (ref "C2") (pin "2") (pinfunction "2_2") (pintype "passive"))
      (node (ref "C20") (pin "1") (pinfunction "1_1") (pintype "passive"))
      (node (ref "C21") (pin "1") (pinfunction "1_1") (pintype "passive"))
      (node (ref "C22") (pin "1") (pinfunction "1_1") (pintype "passive"))
      (node (ref "C23") (pin "1") (pinfunction "1_1") (pintype "passive"))
      (node (ref "C24") (pin "1") (pinfunction "1_1") (pintype "passive"))
      (node (ref "C25") (pin "1") (pinfunction "1_1") (pintype "passive"))
      (node (ref "C26") (pin "1") (pinfunction "1_1") (pintype "passive"))
      (node (ref "C27") (pin "1") (pinfunction "1_1") (pintype "passive"))
      (node (ref "C28") (pin "1") (pinfunction "1_1") (pintype "passive"))
      (node (ref "C29") (pin "1") (pinfunction "1_1") (pintype "passive"))
      (node (ref "C3") (pin "1") (pinfunction "1_1") (pintype "passive"))
      (node (ref "C30") (pin "1") (pinfunction "1_1") (pintype "passive"))
      (node (ref "C31") (pin "1") (pinfunction "1_1") (pintype "passive"))
      (node (ref "C32") (pin "1") (pinfunction "1_1") (pintype "passive"))
      (node (ref "C33") (pin "1") (pinfunction "1_1") (pintype "passive"))
      (node (ref "C34") (pin "1") (pinfunction "1_1") (pintype "passive"))
      (node (ref "C4") (pin "1") (pinfunction "1_1") (pintype "passive"))
      (node (ref "C5") (pin "1") (pinfunction "1_1") (pintype "passive"))
      (node (ref "C6") (pin "1") (pinfunction "1_1") (pintype "passive"))
      (node (ref "C7") (pin "1") (pinfunction "1_1") (pintype "passive"))
      (node (ref "C8") (pin "1") (pinfunction "1_1") (pintype "passive"))
      (node (ref "C9") (pin "1") (pinfunction "1_1") (pintype "passive"))
      (node (ref "D1") (pin "2") (pinfunction "Cathode_2") (pintype "passive"))
      (node (ref "J1") (pin "6") (pinfunction "6_6") (pintype "passive"))
      (node (ref "J1") (pin "7") (pinfunction "7_7") (pintype "passive"))
      (node (ref "J4") (pin "7") (pinfunction "7_7") (pintype "passive"))
      (node (ref "J5") (pin "6") (pinfunction "6_6") (pintype "passive"))
      (node (ref "J6") (pin "6") (pinfunction "6_6") (pintype "passive"))
      (node (ref "J7") (pin "10") (pinfunction "10_10") (pintype "passive"))
      (node (ref "J7") (pin "11") (pinfunction "11_11") (pintype "passive"))
      (node (ref "J7") (pin "5") (pinfunction "5_5") (pintype "passive"))
      (node (ref "J7") (pin "6") (pinfunction "6_6") (pintype "passive"))
      (node (ref "J7") (pin "7") (pinfunction "7_7") (pintype "passive"))
      (node (ref "J7") (pin "8") (pinfunction "8_8") (pintype "passive"))
      (node (ref "J7") (pin "9") (pinfunction "9_9") (pintype "passive"))
      (node (ref "J9") (pin "1") (pinfunction "1_1") (pintype "passive"))
      (node (ref "MH1") (pin "1") (pinfunction "1_1") (pintype "passive"))
      (node (ref "MH2") (pin "1") (pinfunction "1_1") (pintype "passive"))
      (node (ref "MH3") (pin "1") (pinfunction "1_1") (pintype "passive"))
      (node (ref "R12") (pin "1") (pinfunction "1_1") (pintype "passive"))
      (node (ref "R8") (pin "2") (pinfunction "2_2") (pintype "passive"))
      (node (ref "SW1") (pin "3") (pinfunction "3_3") (pintype "passive"))
      (node (ref "SW1") (pin "4") (pinfunction "4_4") (pintype "passive"))
      (node (ref "SW2") (pin "3") (pinfunction "3_3") (pintype "passive"))
      (node (ref "SW2") (pin "4") (pinfunction "4_4") (pintype "passive"))
      (node (ref "U1") (pin "22") (pinfunction "GND_22") (pintype "passive"))
      (node (ref "U1") (pin "8") (pinfunction "GND_8") (pintype "passive"))
      (node (ref "U2") (pin "28") (pinfunction "UGND_28") (pintype "power_in"))
      (node (ref "U2") (pin "3") (pinfunction "GND_3") (pintype "power_in"))
      (node (ref "U3") (pin "3") (pinfunction "GND_3") (pintype "passive"))
      (node (ref "U3") (pin "6") (pinfunction "EPAD_6") (pintype "passive"))
      (node (ref "U4") (pin "3") (pinfunction "3_3") (pintype "passive"))
      (node (ref "U5") (pin "3") (pinfunction "3_3") (pintype "passive"))
      (node (ref "U6") (pin "3") (pinfunction "3_3") (pintype "passive"))
      (node (ref "U7") (pin "3") (pinfunction "3_3") (pintype "passive"))
      (node (ref "Z1") (pin "1") (pinfunction "1_1") (pintype "passive"))
      (node (ref "Z2") (pin "1") (pinfunction "1_1") (pintype "passive"))
    )
    (net (code "62") (name "Net-(C11-Pad2)") (class "Default")
      (node (ref "C11") (pin "2") (pinfunction "2_2") (pintype "passive"))
      (node (ref "JP1") (pin "1") (pinfunction "1_1") (pintype "passive"))
    )
    (net (code "63") (name "Net-(D1-Anode)") (class "Default")
      (node (ref "D1") (pin "1") (pinfunction "Anode_1") (pintype "passive"))
      (node (ref "R17") (pin "1") (pinfunction "1_1") (pintype "passive"))
    )
    (net (code "64") (name "Net-(D2-Anode)") (class "Default")
      (node (ref "D2") (pin "1") (pinfunction "Anode_1") (pintype "passive"))
      (node (ref "R15") (pin "1") (pinfunction "1_1") (pintype "passive"))
    )
    (net (code "65") (name "Net-(D2-Cathode)") (class "Default")
      (node (ref "D2") (pin "2") (pinfunction "Cathode_2") (pintype "passive"))
      (node (ref "U4") (pin "4") (pinfunction "4_4") (pintype "output"))
    )
    (net (code "66") (name "Net-(D3-Anode)") (class "Default")
      (node (ref "D3") (pin "1") (pinfunction "Anode_1") (pintype "passive"))
      (node (ref "R2") (pin "1") (pinfunction "1_1") (pintype "passive"))
    )
    (net (code "67") (name "Net-(D4-Anode)") (class "Default")
      (node (ref "D4") (pin "1") (pinfunction "Anode_1") (pintype "passive"))
      (node (ref "R3") (pin "1") (pinfunction "1_1") (pintype "passive"))
    )
    (net (code "68") (name "Net-(D5-Anode)") (class "Default")
      (node (ref "D5") (pin "1") (pinfunction "Anode_1") (pintype "passive"))
      (node (ref "R19") (pin "1") (pinfunction "1_1") (pintype "passive"))
      (node (ref "R23") (pin "1") (pinfunction "1_1") (pintype "passive"))
    )
    (net (code "69") (name "Net-(J7-Pad4)") (class "Default")
      (node (ref "J7") (pin "4") (pinfunction "4_4") (pintype "passive"))
      (node (ref "R8") (pin "1") (pinfunction "1_1") (pintype "passive"))
    )
    (net (code "70") (name "Net-(JP1-Pad3)") (class "Default")
      (node (ref "JP1") (pin "3") (pinfunction "3_3") (pintype "passive"))
      (node (ref "R12") (pin "2") (pinfunction "2_2") (pintype "passive"))
    )
    (net (code "71") (name "Net-(R22-Pad1)") (class "Default")
      (node (ref "R22") (pin "1") (pinfunction "1_1") (pintype "passive"))
      (node (ref "U7") (pin "4") (pinfunction "4_4") (pintype "output"))
    )
    (net (code "72") (name "unconnected-(J1-Pad1)") (class "Default")
      (node (ref "J1") (pin "1") (pinfunction "1_1") (pintype "passive+no_connect"))
    )
    (net (code "73") (name "unconnected-(J1-Pad8)") (class "Default")
      (node (ref "J1") (pin "8") (pinfunction "8_8") (pintype "passive+no_connect"))
    )
    (net (code "74") (name "unconnected-(MH4-Pad1)") (class "Default")
      (node (ref "MH4") (pin "1") (pinfunction "1_1") (pintype "passive+no_connect"))
    )
    (net (code "75") (name "unconnected-(U2-PC2_(PCINT11{slash}AIN2)-Pad5)") (class "Default")
      (node (ref "U2") (pin "5") (pinfunction "PC2_(PCINT11/AIN2)_5") (pintype "passive+no_connect"))
    )
    (net (code "76") (name "unconnected-(U2-PC4_(PCINT10)-Pad26)") (class "Default")
      (node (ref "U2") (pin "26") (pinfunction "PC4_(PCINT10)_26") (pintype "passive+no_connect"))
    )
    (net (code "77") (name "unconnected-(U2-PC5_(PCINT9{slash}OC.1B)-Pad25)") (class "Default")
      (node (ref "U2") (pin "25") (pinfunction "PC5_(PCINT9/OC.1B)_25") (pintype "passive+no_connect"))
    )
    (net (code "78") (name "unconnected-(U2-PC6_(OC.1A{slash}PCINT8)-Pad23)") (class "Default")
      (node (ref "U2") (pin "23") (pinfunction "PC6_(OC.1A/PCINT8)_23") (pintype "passive+no_connect"))
    )
    (net (code "79") (name "unconnected-(U2-PC7_(INT4{slash}ICP1{slash}CLKO)-Pad22)") (class "Default")
      (node (ref "U2") (pin "22") (pinfunction "PC7_(INT4/ICP1/CLKO)_22") (pintype "passive+no_connect"))
    )
    (net (code "80") (name "unconnected-(U2-PD0_(OC.0B{slash}INT0)-Pad6)") (class "Default")
      (node (ref "U2") (pin "6") (pinfunction "PD0_(OC.0B/INT0)_6") (pintype "passive+no_connect"))
    )
    (net (code "81") (name "unconnected-(U2-PD1_(AIN0{slash}INT1)-Pad7)") (class "Default")
      (node (ref "U2") (pin "7") (pinfunction "PD1_(AIN0/INT1)_7") (pintype "passive+no_connect"))
    )
    (net (code "82") (name "unconnected-(U2-PD6_(~{RTS}{slash}AIN5{slash}INT6)-Pad12)") (class "Default")
      (node (ref "U2") (pin "12") (pinfunction "PD6_(~{RTS}/AIN5/INT6)_12") (pintype "passive"))
    )
    (net (code "83") (name "unconnected-(U2-~{SS}{slash}_PCINT0_{slash}_PB0-Pad14)") (class "Default")
      (node (ref "U2") (pin "14") (pinfunction "~{SS}/_PCINT0_/_PB0_14") (pintype "passive+no_connect"))
    )
  )
)
